# debug_leds.net
KiCad netlist of a schematic drawn in Altium Designer
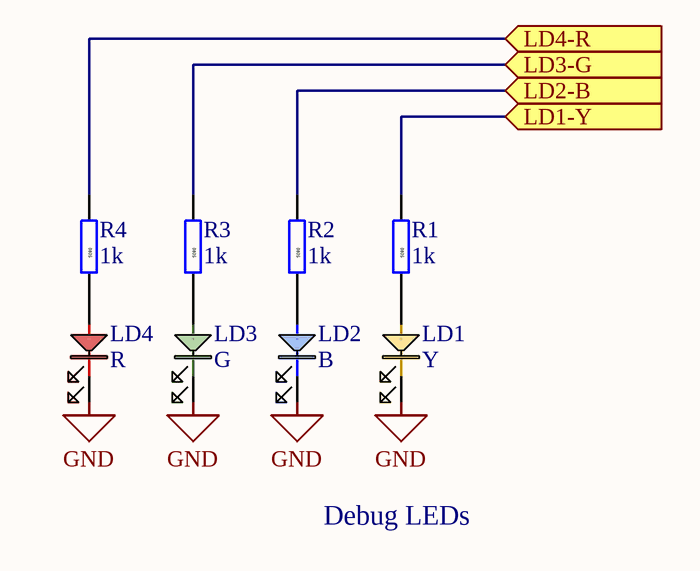
[diagram p0: debug_leds.SchDoc]

(export (version "E")
  (design (tool "Eeschema 10.0.6"))
  (components
    (comp (ref "LD1")
      (value "Y")
      (footprint "0603_LED_Y")
      (description "0603 Yellow Led")
      (fields (field (name "JLCPCB PART") "C7496811"))
      (libsource (lib "Kubikova ultra knihovna") (part "LED Y 0603"))
    )
    (comp (ref "LD2")
      (value "B")
      (footprint "0603_LED_B")
      (description "0603 Blue Led")
      (fields (field (name "JLCPCB PART") "C7496819"))
      (libsource (lib "Kubikova ultra knihovna") (part "LED B 0603"))
    )
    (comp (ref "LD3")
      (value "G")
      (footprint "0603_LED_G")
      (description "0603 Green Led")
      (fields (field (name "JLCPCB PART") "C22371297"))
      (libsource (lib "Kubikova ultra knihovna") (part "LED G 0603"))
    )
    (comp (ref "LD4")
      (value "R")
      (footprint "0603_LED_R")
      (description "-40℃~+85℃ Red 0603 LED Indication - Discrete ROHS")
      (fields (field (name "JLCPCB PART") "C2286"))
      (libsource (lib "Kubikova ultra knihovna") (part "LED R 0603"))
    )
    (comp (ref "R1")
      (value "1k")
      (footprint "RESC2012X06N(SMR0805)")
      (description "125mW Thick Film Resistors 150V ±100ppm/℃ ±1% 1kΩ 0805 Chip Resistor - Surface Mount ROHS")
      (fields (field (name "JLCPCB PART") "C17513") (field (name "AUTHOR") "JP/27.03.2014"))
      (libsource (lib "Kubikova ultra knihovna") (part "Res 1k 0805"))
    )
    (comp (ref "R2")
      (value "1k")
      (footprint "RESC2012X06N(SMR0805)")
      (description "125mW Thick Film Resistors 150V ±100ppm/℃ ±1% 1kΩ 0805 Chip Resistor - Surface Mount ROHS")
      (fields (field (name "JLCPCB PART") "C17513") (field (name "AUTHOR") "JP/27.03.2014"))
      (libsource (lib "Kubikova ultra knihovna") (part "Res 1k 0805"))
    )
    (comp (ref "R3")
      (value "1k")
      (footprint "RESC2012X06N(SMR0805)")
      (description "125mW Thick Film Resistors 150V ±100ppm/℃ ±1% 1kΩ 0805 Chip Resistor - Surface Mount ROHS")
      (fields (field (name "JLCPCB PART") "C17513") (field (name "AUTHOR") "JP/27.03.2014"))
      (libsource (lib "Kubikova ultra knihovna") (part "Res 1k 0805"))
    )
    (comp (ref "R4")
      (value "1k")
      (footprint "RESC2012X06N(SMR0805)")
      (description "125mW Thick Film Resistors 150V ±100ppm/℃ ±1% 1kΩ 0805 Chip Resistor - Surface Mount ROHS")
      (fields (field (name "JLCPCB PART") "C17513") (field (name "AUTHOR") "JP/27.03.2014"))
      (libsource (lib "Kubikova ultra knihovna") (part "Res 1k 0805"))
    )
  )
  (nets
    (net (code "1") (name "/LD1-Y") (class "Default")
      (node (ref "R1") (pin "1") (pinfunction "1_1") (pintype "passive"))
    )
    (net (code "2") (name "/LD2-B") (class "Default")
      (node (ref "R2") (pin "1") (pinfunction "1_1") (pintype "passive"))
    )
    (net (code "3") (name "/LD3-G") (class "Default")
      (node (ref "R3") (pin "1") (pinfunction "1_1") (pintype "passive"))
    )
    (net (code "4") (name "/LD4-R") (class "Default")
      (node (ref "R4") (pin "1") (pinfunction "1_1") (pintype "passive"))
    )
    (net (code "5") (name "GND") (class "Default")
      (node (ref "LD1") (pin "2") (pintype "passive"))
      (node (ref "LD2") (pin "2") (pintype "passive"))
      (node (ref "LD3") (pin "2") (pintype "passive"))
      (node (ref "LD4") (pin "2") (pintype "passive"))
    )
    (net (code "6") (name "Net-(LD1-Pad1)") (class "Default")
      (node (ref "LD1") (pin "1") (pintype "passive"))
      (node (ref "R1") (pin "2") (pinfunction "2_2") (pintype "passive"))
    )
    (net (code "7") (name "Net-(LD2-Pad1)") (class "Default")
      (node (ref "LD2") (pin "1") (pintype "passive"))
      (node (ref "R2") (pin "2") (pinfunction "2_2") (pintype "passive"))
    )
    (net (code "8") (name "Net-(LD3-Pad1)") (class "Default")
      (node (ref "LD3") (pin "1") (pintype "passive"))
      (node (ref "R3") (pin "2") (pinfunction "2_2") (pintype "passive"))
    )
    (net (code "9") (name "Net-(LD4-Pad1)") (class "Default")
      (node (ref "LD4") (pin "1") (pintype "passive"))
      (node (ref "R4") (pin "2") (pinfunction "2_2") (pintype "passive"))
    )
  )
)
